# Power.net
KiCad netlist of a schematic drawn in Altium Designer
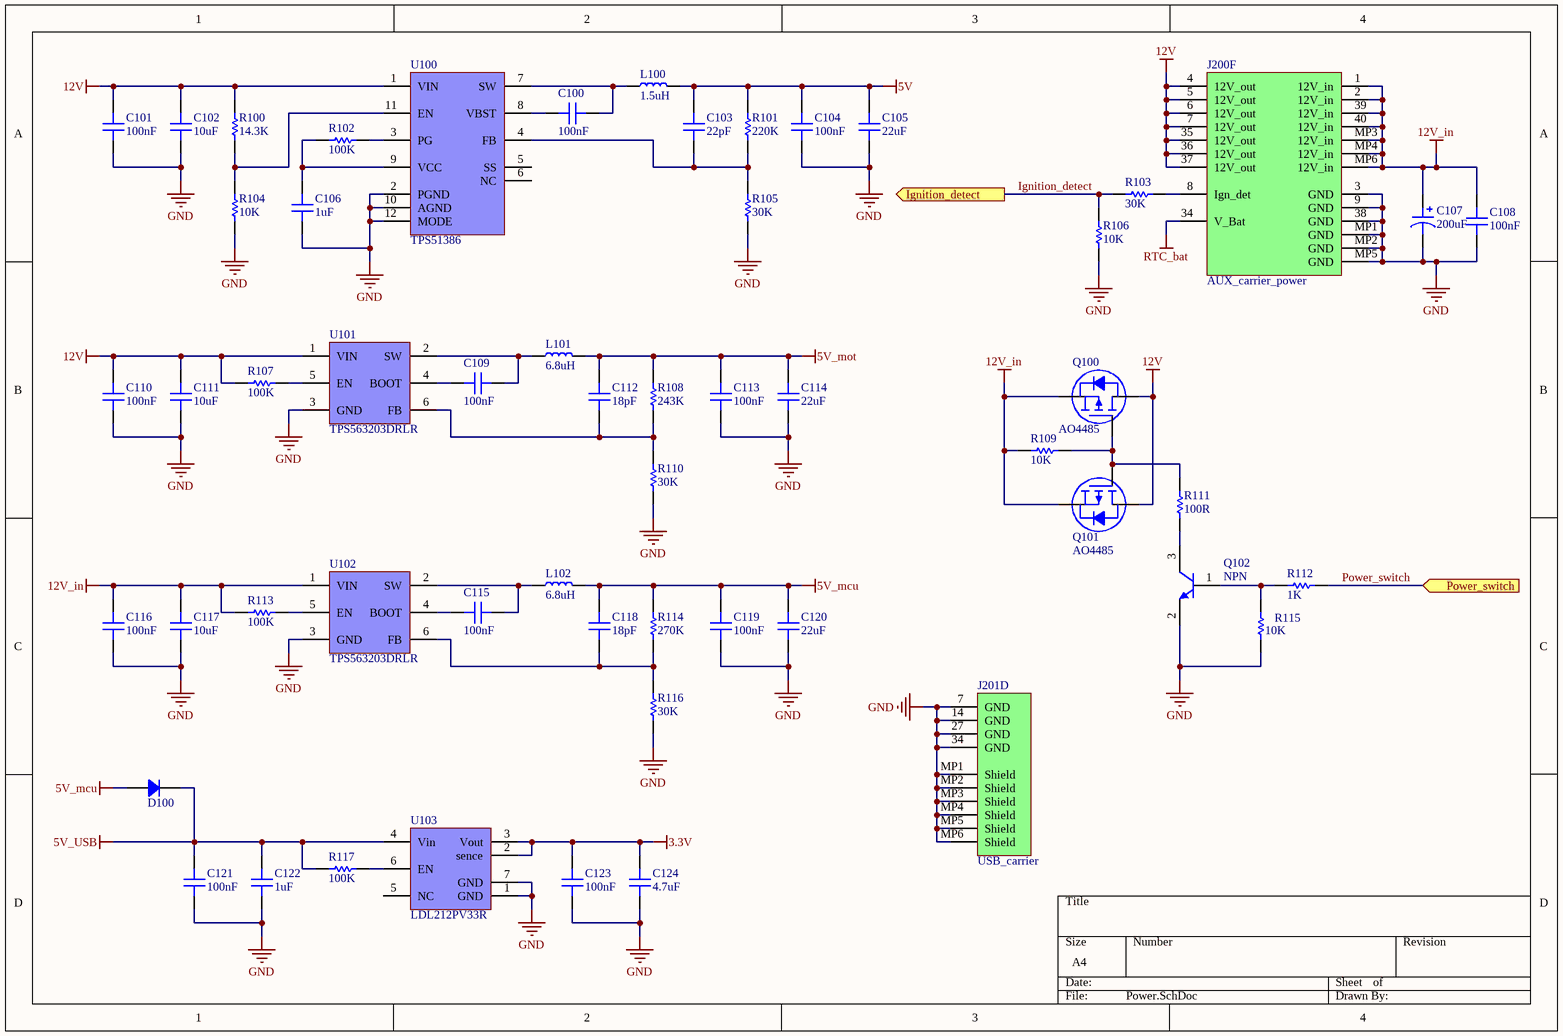
[diagram p0: Power.SchDoc]

(export (version "E")
  (design (tool "Eeschema 10.0.6"))
  (components
    (comp (ref "C100")
      (value "100nF")
      (footprint "CAP 0603")
      (description "SMT Capacitor")
      (libsource (lib "Schlib1") (part "Capacitor"))
    )
    (comp (ref "C101")
      (value "100nF")
      (footprint "CAP 0603")
      (description "SMT Capacitor")
      (libsource (lib "Schlib1") (part "Capacitor"))
    )
    (comp (ref "C102")
      (value "10uF")
      (footprint "CAP 1206")
      (description "SMT Capacitor")
      (libsource (lib "Schlib1") (part "Capacitor"))
    )
    (comp (ref "C103")
      (value "22pF")
      (footprint "CAP 0603")
      (description "SMT Capacitor")
      (libsource (lib "Schlib1") (part "Capacitor"))
    )
    (comp (ref "C104")
      (value "100nF")
      (footprint "CAP 0603")
      (description "SMT Capacitor")
      (libsource (lib "Schlib1") (part "Capacitor"))
    )
    (comp (ref "C105")
      (value "22uF")
      (footprint "CAP 1206")
      (description "SMT Capacitor")
      (libsource (lib "Schlib1") (part "Capacitor"))
    )
    (comp (ref "C106")
      (value "1uF")
      (footprint "CAP 0603")
      (description "SMT Capacitor")
      (libsource (lib "Schlib1") (part "Capacitor"))
    )
    (comp (ref "C107")
      (value "200uF")
      (footprint "CAP ALSMD ELEC 6.6MM H5.7MM")
      (description "SMT Polarised Capacitor")
      (libsource (lib "Schlib1") (part "Capacitor polarized"))
    )
    (comp (ref "C108")
      (value "100nF")
      (footprint "CAP 0603")
      (description "SMT Capacitor")
      (libsource (lib "Schlib1") (part "Capacitor"))
    )
    (comp (ref "C109")
      (value "100nF")
      (footprint "CAP 0603")
      (description "SMT Capacitor")
      (libsource (lib "Schlib1") (part "Capacitor"))
    )
    (comp (ref "C110")
      (value "100nF")
      (footprint "CAP 0603")
      (description "SMT Capacitor")
      (libsource (lib "Schlib1") (part "Capacitor"))
    )
    (comp (ref "C111")
      (value "10uF")
      (footprint "CAP 1206")
      (description "SMT Capacitor")
      (libsource (lib "Schlib1") (part "Capacitor"))
    )
    (comp (ref "C112")
      (value "18pF")
      (footprint "CAP 0603")
      (description "SMT Capacitor")
      (libsource (lib "Schlib1") (part "Capacitor"))
    )
    (comp (ref "C113")
      (value "100nF")
      (footprint "CAP 0603")
      (description "SMT Capacitor")
      (libsource (lib "Schlib1") (part "Capacitor"))
    )
    (comp (ref "C114")
      (value "22uF")
      (footprint "CAP 1206")
      (description "SMT Capacitor")
      (libsource (lib "Schlib1") (part "Capacitor"))
    )
    (comp (ref "C115")
      (value "100nF")
      (footprint "CAP 0603")
      (description "SMT Capacitor")
      (libsource (lib "Schlib1") (part "Capacitor"))
    )
    (comp (ref "C116")
      (value "100nF")
      (footprint "CAP 0603")
      (description "SMT Capacitor")
      (libsource (lib "Schlib1") (part "Capacitor"))
    )
    (comp (ref "C117")
      (value "10uF")
      (footprint "CAP 1206")
      (description "SMT Capacitor")
      (libsource (lib "Schlib1") (part "Capacitor"))
    )
    (comp (ref "C118")
      (value "18pF")
      (footprint "CAP 0603")
      (description "SMT Capacitor")
      (libsource (lib "Schlib1") (part "Capacitor"))
    )
    (comp (ref "C119")
      (value "100nF")
      (footprint "CAP 0603")
      (description "SMT Capacitor")
      (libsource (lib "Schlib1") (part "Capacitor"))
    )
    (comp (ref "C120")
      (value "22uF")
      (footprint "CAP 1206")
      (description "SMT Capacitor")
      (libsource (lib "Schlib1") (part "Capacitor"))
    )
    (comp (ref "C121")
      (value "100nF")
      (footprint "CAP 0603")
      (description "SMT Capacitor")
      (libsource (lib "Schlib1") (part "Capacitor"))
    )
    (comp (ref "C122")
      (value "1uF")
      (footprint "CAP 0603")
      (description "SMT Capacitor")
      (libsource (lib "Schlib1") (part "Capacitor"))
    )
    (comp (ref "C123")
      (value "100nF")
      (footprint "CAP 0603")
      (description "SMT Capacitor")
      (libsource (lib "Schlib1") (part "Capacitor"))
    )
    (comp (ref "C124")
      (value "4.7uF")
      (footprint "CAP 1206")
      (description "SMT Capacitor")
      (libsource (lib "Schlib1") (part "Capacitor"))
    )
    (comp (ref "D100")
      (value "~")
      (footprint "Bourns DO214AC SMA - duplicate")
      (description "Rectifier Diode")
      (libsource (lib "Schlib1") (part "Diode"))
    )
    (comp (ref "J200")
      (value "AUX_carrier_power")
      (footprint "2167010409")
      (libsource (lib "Schlib1") (part "AUX_carrier"))
    )
    (comp (ref "J201")
      (value "USB_carrier")
      (footprint "2167010409")
      (libsource (lib "Schlib1") (part "USB_carrier"))
    )
    (comp (ref "L100")
      (value "1.5uH")
      (footprint "IND 0806_2016")
      (description "SMT Inductor")
      (libsource (lib "Schlib1") (part "Inductor"))
    )
    (comp (ref "L101")
      (value "6.8uH")
      (footprint "IND 0806_2016")
      (description "SMT Inductor")
      (libsource (lib "Schlib1") (part "Inductor"))
    )
    (comp (ref "L102")
      (value "6.8uH")
      (footprint "IND 0806_2016")
      (description "SMT Inductor")
      (libsource (lib "Schlib1") (part "Inductor"))
    )
    (comp (ref "Q100")
      (value "AO4485")
      (footprint "ALPHAOMEGA SO8 SOP-8L AO4485")
      (description "MOSFET P-CH 40V 10A 8SOIC")
      (fields (field (name "MANUFACTURER") "Alpha & Omega Semiconductor Inc."))
      (libsource (lib "") (part "MOSFET P-CH GDS_1"))
    )
    (comp (ref "Q101")
      (value "AO4485")
      (footprint "ALPHAOMEGA SO8 SOP-8L AO4485")
      (description "MOSFET P-CH 40V 10A 8SOIC")
      (fields (field (name "MANUFACTURER") "Alpha & Omega Semiconductor Inc."))
      (libsource (lib "Celestial Altium Library - altium_library") (part "MOSFET P-CH GDS"))
    )
    (comp (ref "Q102") (value "NPN") (footprint "SOT-23") (libsource (lib "Schlib1") (part "NPN")))
    (comp (ref "R100")
      (value "14.3K")
      (footprint "RES 0603")
      (description "Resistor")
      (fields (field (name "PUBLISHER") "Altium Limited"))
      (libsource (lib "Schlib1") (part "Res"))
    )
    (comp (ref "R101")
      (value "220K")
      (footprint "RES 0603")
      (description "Resistor")
      (fields (field (name "PUBLISHER") "Altium Limited"))
      (libsource (lib "Schlib1") (part "Res"))
    )
    (comp (ref "R102")
      (value "100K")
      (footprint "RES 0603")
      (description "Resistor")
      (fields (field (name "PUBLISHER") "Altium Limited"))
      (libsource (lib "Schlib1") (part "Res"))
    )
    (comp (ref "R103")
      (value "30K")
      (footprint "RES 0603")
      (description "Resistor")
      (fields (field (name "PUBLISHER") "Altium Limited"))
      (libsource (lib "Schlib1") (part "Res"))
    )
    (comp (ref "R104")
      (value "10K")
      (footprint "RES 0603")
      (description "Resistor")
      (fields (field (name "PUBLISHER") "Altium Limited"))
      (libsource (lib "Schlib1") (part "Res"))
    )
    (comp (ref "R105")
      (value "30K")
      (footprint "RES 0603")
      (description "Resistor")
      (fields (field (name "PUBLISHER") "Altium Limited"))
      (libsource (lib "Schlib1") (part "Res"))
    )
    (comp (ref "R106")
      (value "10K")
      (footprint "RES 0603")
      (description "Resistor")
      (fields (field (name "PUBLISHER") "Altium Limited"))
      (libsource (lib "Schlib1") (part "Res"))
    )
    (comp (ref "R107")
      (value "100K")
      (footprint "RES 0603")
      (description "Resistor")
      (fields (field (name "PUBLISHER") "Altium Limited"))
      (libsource (lib "Schlib1") (part "Res"))
    )
    (comp (ref "R108")
      (value "243K")
      (footprint "RES 0603")
      (description "Resistor")
      (fields (field (name "PUBLISHER") "Altium Limited"))
      (libsource (lib "Schlib1") (part "Res"))
    )
    (comp (ref "R109")
      (value "10K")
      (footprint "RES 0603")
      (description "Resistor")
      (fields (field (name "PUBLISHER") "Altium Limited"))
      (libsource (lib "Schlib1") (part "Res"))
    )
    (comp (ref "R110")
      (value "30K")
      (footprint "RES 0603")
      (description "Resistor")
      (fields (field (name "PUBLISHER") "Altium Limited"))
      (libsource (lib "Schlib1") (part "Res"))
    )
    (comp (ref "R111")
      (value "100R")
      (footprint "RES 0603")
      (description "Resistor")
      (fields (field (name "PUBLISHER") "Altium Limited"))
      (libsource (lib "Schlib1") (part "Res"))
    )
    (comp (ref "R112")
      (value "1K")
      (footprint "RES 0603")
      (description "Resistor")
      (fields (field (name "PUBLISHER") "Altium Limited"))
      (libsource (lib "Schlib1") (part "Res"))
    )
    (comp (ref "R113")
      (value "100K")
      (footprint "RES 0603")
      (description "Resistor")
      (fields (field (name "PUBLISHER") "Altium Limited"))
      (libsource (lib "Schlib1") (part "Res"))
    )
    (comp (ref "R114")
      (value "270K")
      (footprint "RES 0603")
      (description "Resistor")
      (fields (field (name "PUBLISHER") "Altium Limited"))
      (libsource (lib "Schlib1") (part "Res"))
    )
    (comp (ref "R115")
      (value "10K")
      (footprint "RES 0603")
      (description "Resistor")
      (fields (field (name "PUBLISHER") "Altium Limited"))
      (libsource (lib "Schlib1") (part "Res"))
    )
    (comp (ref "R116")
      (value "30K")
      (footprint "RES 0603")
      (description "Resistor")
      (fields (field (name "PUBLISHER") "Altium Limited"))
      (libsource (lib "Schlib1") (part "Res"))
    )
    (comp (ref "R117")
      (value "100K")
      (footprint "RES 0603")
      (description "Resistor")
      (fields (field (name "PUBLISHER") "Altium Limited"))
      (libsource (lib "Schlib1") (part "Res"))
    )
    (comp (ref "U100")
      (value "TPS51386")
      (footprint "VREG_TPS51386RJNR")
      (libsource (lib "Schlib1") (part "TPS51386"))
    )
    (comp (ref "U101")
      (value "TPS563203DRLR")
      (footprint "TI SOT-563 DRL")
      (libsource (lib "Schlib1") (part "TPS563203DRLR"))
    )
    (comp (ref "U102")
      (value "TPS563203DRLR")
      (footprint "TI SOT-563 DRL")
      (libsource (lib "Schlib1") (part "TPS563203DRLR"))
    )
    (comp (ref "U103")
      (value "LDL212PV33R")
      (footprint "SON50P200X200X80-7N-D")
      (libsource (lib "Schlib1") (part "LDL212PV33R"))
    )
  )
  (nets
    (net (code "1") (name "/Ignition_detect") (class "Default")
      (node (ref "R103") (pin "2") (pinfunction "2_2") (pintype "passive"))
      (node (ref "R106") (pin "1") (pinfunction "1_1") (pintype "passive"))
    )
    (net (code "2") (name "/Power_switch") (class "Default")
      (node (ref "R112") (pin "1") (pinfunction "1_1") (pintype "passive"))
    )
    (net (code "3") (name "3.3V") (class "Default")
      (node (ref "C123") (pin "2") (pinfunction "2_2") (pintype "passive"))
      (node (ref "C124") (pin "2") (pinfunction "2_2") (pintype "passive"))
      (node (ref "U103") (pin "2") (pinfunction "sence_2") (pintype "passive"))
      (node (ref "U103") (pin "3") (pinfunction "Vout_3") (pintype "passive"))
    )
    (net (code "4") (name "5V") (class "Default")
      (node (ref "C103") (pin "2") (pinfunction "2_2") (pintype "passive"))
      (node (ref "C104") (pin "2") (pinfunction "2_2") (pintype "passive"))
      (node (ref "C105") (pin "2") (pinfunction "2_2") (pintype "passive"))
      (node (ref "L100") (pin "2") (pinfunction "2_2") (pintype "passive"))
      (node (ref "R101") (pin "2") (pinfunction "2_2") (pintype "passive"))
    )
    (net (code "5") (name "5V_USB") (class "Default")
      (node (ref "C121") (pin "2") (pinfunction "2_2") (pintype "passive"))
      (node (ref "C122") (pin "2") (pinfunction "2_2") (pintype "passive"))
      (node (ref "D100") (pin "2") (pinfunction "2_2") (pintype "passive"))
      (node (ref "R117") (pin "1") (pinfunction "1_1") (pintype "passive"))
      (node (ref "U103") (pin "4") (pinfunction "Vin_4") (pintype "passive"))
    )
    (net (code "6") (name "5V_mcu") (class "Default")
      (node (ref "C118") (pin "2") (pinfunction "2_2") (pintype "passive"))
      (node (ref "C119") (pin "2") (pinfunction "2_2") (pintype "passive"))
      (node (ref "C120") (pin "2") (pinfunction "2_2") (pintype "passive"))
      (node (ref "D100") (pin "1") (pinfunction "1_1") (pintype "passive"))
      (node (ref "L102") (pin "2") (pinfunction "2_2") (pintype "passive"))
      (node (ref "R114") (pin "2") (pinfunction "2_2") (pintype "passive"))
    )
    (net (code "7") (name "5V_mot") (class "Default")
      (node (ref "C112") (pin "2") (pinfunction "2_2") (pintype "passive"))
      (node (ref "C113") (pin "2") (pinfunction "2_2") (pintype "passive"))
      (node (ref "C114") (pin "2") (pinfunction "2_2") (pintype "passive"))
      (node (ref "L101") (pin "2") (pinfunction "2_2") (pintype "passive"))
      (node (ref "R108") (pin "2") (pinfunction "2_2") (pintype "passive"))
    )
    (net (code "8") (name "12V") (class "Default")
      (node (ref "C101") (pin "2") (pinfunction "2_2") (pintype "passive"))
      (node (ref "C102") (pin "2") (pinfunction "2_2") (pintype "passive"))
      (node (ref "C110") (pin "2") (pinfunction "2_2") (pintype "passive"))
      (node (ref "C111") (pin "2") (pinfunction "2_2") (pintype "passive"))
      (node (ref "J200") (pin "35") (pinfunction "12V_out_35") (pintype "passive"))
      (node (ref "J200") (pin "36") (pinfunction "12V_out_36") (pintype "passive"))
      (node (ref "J200") (pin "37") (pinfunction "12V_out_37") (pintype "passive"))
      (node (ref "J200") (pin "4") (pinfunction "12V_out_4") (pintype "passive"))
      (node (ref "J200") (pin "5") (pinfunction "12V_out_5") (pintype "passive"))
      (node (ref "J200") (pin "6") (pinfunction "12V_out_6") (pintype "passive"))
      (node (ref "J200") (pin "7") (pinfunction "12V_out_7") (pintype "passive"))
      (node (ref "Q100") (pin "D") (pinfunction "D_D") (pintype "passive"))
      (node (ref "Q101") (pin "D") (pinfunction "D_D") (pintype "passive"))
      (node (ref "R100") (pin "1") (pinfunction "1_1") (pintype "passive"))
      (node (ref "R107") (pin "1") (pinfunction "1_1") (pintype "passive"))
      (node (ref "U100") (pin "1") (pinfunction "VIN_1") (pintype "passive"))
      (node (ref "U101") (pin "1") (pinfunction "VIN_1") (pintype "passive"))
    )
    (net (code "9") (name "12V_in") (class "Default")
      (node (ref "C107") (pin "2") (pinfunction "2_2") (pintype "passive"))
      (node (ref "C108") (pin "2") (pinfunction "2_2") (pintype "passive"))
      (node (ref "C116") (pin "2") (pinfunction "2_2") (pintype "passive"))
      (node (ref "C117") (pin "2") (pinfunction "2_2") (pintype "passive"))
      (node (ref "J200") (pin "1") (pinfunction "12V_in_1") (pintype "passive"))
      (node (ref "J200") (pin "2") (pinfunction "12V_in_2") (pintype "passive"))
      (node (ref "J200") (pin "39") (pinfunction "12V_in_39") (pintype "passive"))
      (node (ref "J200") (pin "40") (pinfunction "12V_in_40") (pintype "passive"))
      (node (ref "J200") (pin "MP3") (pinfunction "12V_in_MP3") (pintype "passive"))
      (node (ref "J200") (pin "MP4") (pinfunction "12V_in_MP4") (pintype "passive"))
      (node (ref "J200") (pin "MP6") (pinfunction "12V_in_MP6") (pintype "passive"))
      (node (ref "Q100") (pin "S") (pinfunction "S_S") (pintype "passive"))
      (node (ref "Q101") (pin "S") (pinfunction "S_S") (pintype "passive"))
      (node (ref "R109") (pin "2") (pinfunction "2_2") (pintype "passive"))
      (node (ref "R113") (pin "1") (pinfunction "1_1") (pintype "passive"))
      (node (ref "U102") (pin "1") (pinfunction "VIN_1") (pintype "passive"))
    )
    (net (code "10") (name "GND") (class "Default")
      (node (ref "C101") (pin "1") (pinfunction "1_1") (pintype "passive"))
      (node (ref "C102") (pin "1") (pinfunction "1_1") (pintype "passive"))
      (node (ref "C104") (pin "1") (pinfunction "1_1") (pintype "passive"))
      (node (ref "C105") (pin "1") (pinfunction "1_1") (pintype "passive"))
      (node (ref "C106") (pin "1") (pinfunction "1_1") (pintype "passive"))
      (node (ref "C107") (pin "1") (pinfunction "1_1") (pintype "passive"))
      (node (ref "C108") (pin "1") (pinfunction "1_1") (pintype "passive"))
      (node (ref "C110") (pin "1") (pinfunction "1_1") (pintype "passive"))
      (node (ref "C111") (pin "1") (pinfunction "1_1") (pintype "passive"))
      (node (ref "C113") (pin "1") (pinfunction "1_1") (pintype "passive"))
      (node (ref "C114") (pin "1") (pinfunction "1_1") (pintype "passive"))
      (node (ref "C116") (pin "1") (pinfunction "1_1") (pintype "passive"))
      (node (ref "C117") (pin "1") (pinfunction "1_1") (pintype "passive"))
      (node (ref "C119") (pin "1") (pinfunction "1_1") (pintype "passive"))
      (node (ref "C120") (pin "1") (pinfunction "1_1") (pintype "passive"))
      (node (ref "C121") (pin "1") (pinfunction "1_1") (pintype "passive"))
      (node (ref "C122") (pin "1") (pinfunction "1_1") (pintype "passive"))
      (node (ref "C123") (pin "1") (pinfunction "1_1") (pintype "passive"))
      (node (ref "C124") (pin "1") (pinfunction "1_1") (pintype "passive"))
      (node (ref "J200") (pin "3") (pinfunction "GND_3") (pintype "passive"))
      (node (ref "J200") (pin "38") (pinfunction "GND_38") (pintype "passive"))
      (node (ref "J200") (pin "9") (pinfunction "GND_9") (pintype "passive"))
      (node (ref "J200") (pin "MP1") (pinfunction "GND_MP1") (pintype "passive"))
      (node (ref "J200") (pin "MP2") (pinfunction "GND_MP2") (pintype "passive"))
      (node (ref "J200") (pin "MP5") (pinfunction "GND_MP5") (pintype "passive"))
      (node (ref "J201") (pin "14") (pinfunction "GND_14") (pintype "passive"))
      (node (ref "J201") (pin "27") (pinfunction "GND_27") (pintype "passive"))
      (node (ref "J201") (pin "34") (pinfunction "GND_34") (pintype "passive"))
      (node (ref "J201") (pin "7") (pinfunction "GND_7") (pintype "passive"))
      (node (ref "J201") (pin "MP1") (pinfunction "Shield_MP1") (pintype "passive"))
      (node (ref "J201") (pin "MP2") (pinfunction "Shield_MP2") (pintype "passive"))
      (node (ref "J201") (pin "MP3") (pinfunction "Shield_MP3") (pintype "passive"))
      (node (ref "J201") (pin "MP4") (pinfunction "Shield_MP4") (pintype "passive"))
      (node (ref "J201") (pin "MP5") (pinfunction "Shield_MP5") (pintype "passive"))
      (node (ref "J201") (pin "MP6") (pinfunction "Shield_MP6") (pintype "passive"))
      (node (ref "Q102") (pin "2") (pinfunction "E_2") (pintype "passive"))
      (node (ref "R104") (pin "1") (pinfunction "1_1") (pintype "passive"))
      (node (ref "R105") (pin "1") (pinfunction "1_1") (pintype "passive"))
      (node (ref "R106") (pin "2") (pinfunction "2_2") (pintype "passive"))
      (node (ref "R110") (pin "1") (pinfunction "1_1") (pintype "passive"))
      (node (ref "R115") (pin "2") (pinfunction "2_2") (pintype "passive"))
      (node (ref "R116") (pin "1") (pinfunction "1_1") (pintype "passive"))
      (node (ref "U100") (pin "10") (pinfunction "AGND_10") (pintype "passive"))
      (node (ref "U100") (pin "12") (pinfunction "MODE_12") (pintype "passive"))
      (node (ref "U100") (pin "2") (pinfunction "PGND_2") (pintype "passive"))
      (node (ref "U101") (pin "3") (pinfunction "GND_3") (pintype "passive"))
      (node (ref "U102") (pin "3") (pinfunction "GND_3") (pintype "passive"))
      (node (ref "U103") (pin "1") (pinfunction "GND_1") (pintype "passive"))
      (node (ref "U103") (pin "7") (pinfunction "GND_7") (pintype "passive"))
    )
    (net (code "11") (name "Net-(J200F-Ign_det)") (class "Default")
      (node (ref "J200") (pin "8") (pinfunction "Ign_det_8") (pintype "passive"))
      (node (ref "R103") (pin "1") (pinfunction "1_1") (pintype "passive"))
    )
    (net (code "12") (name "Net-(Q100-PadG)") (class "Default")
      (node (ref "Q100") (pin "G") (pinfunction "G_G") (pintype "passive"))
      (node (ref "Q101") (pin "G") (pinfunction "G_G") (pintype "passive"))
      (node (ref "R109") (pin "1") (pinfunction "1_1") (pintype "passive"))
      (node (ref "R111") (pin "1") (pinfunction "1_1") (pintype "passive"))
    )
    (net (code "13") (name "Net-(Q102-B)") (class "Default")
      (node (ref "Q102") (pin "1") (pinfunction "B_1") (pintype "passive"))
      (node (ref "R112") (pin "2") (pinfunction "2_2") (pintype "passive"))
      (node (ref "R115") (pin "1") (pinfunction "1_1") (pintype "passive"))
    )
    (net (code "14") (name "Net-(Q102-C)") (class "Default")
      (node (ref "Q102") (pin "3") (pinfunction "C_3") (pintype "passive"))
      (node (ref "R111") (pin "2") (pinfunction "2_2") (pintype "passive"))
    )
    (net (code "15") (name "Net-(U100-EN)") (class "Default")
      (node (ref "R100") (pin "2") (pinfunction "2_2") (pintype "passive"))
      (node (ref "R104") (pin "2") (pinfunction "2_2") (pintype "passive"))
      (node (ref "U100") (pin "11") (pinfunction "EN_11") (pintype "passive"))
    )
    (net (code "16") (name "Net-(U100-FB)") (class "Default")
      (node (ref "C103") (pin "1") (pinfunction "1_1") (pintype "passive"))
      (node (ref "R101") (pin "1") (pinfunction "1_1") (pintype "passive"))
      (node (ref "R105") (pin "2") (pinfunction "2_2") (pintype "passive"))
      (node (ref "U100") (pin "4") (pinfunction "FB_4") (pintype "passive"))
    )
    (net (code "17") (name "Net-(U100-PG)") (class "Default")
      (node (ref "R102") (pin "2") (pinfunction "2_2") (pintype "passive"))
      (node (ref "U100") (pin "3") (pinfunction "PG_3") (pintype "passive"))
    )
    (net (code "18") (name "Net-(U100-SW)") (class "Default")
      (node (ref "C100") (pin "1") (pinfunction "1_1") (pintype "passive"))
      (node (ref "L100") (pin "1") (pinfunction "1_1") (pintype "passive"))
      (node (ref "U100") (pin "7") (pinfunction "SW_7") (pintype "passive"))
    )
    (net (code "19") (name "Net-(U100-VBST)") (class "Default")
      (node (ref "C100") (pin "2") (pinfunction "2_2") (pintype "passive"))
      (node (ref "U100") (pin "8") (pinfunction "VBST_8") (pintype "passive"))
    )
    (net (code "20") (name "Net-(U100-VCC)") (class "Default")
      (node (ref "C106") (pin "2") (pinfunction "2_2") (pintype "passive"))
      (node (ref "R102") (pin "1") (pinfunction "1_1") (pintype "passive"))
      (node (ref "U100") (pin "9") (pinfunction "VCC_9") (pintype "passive"))
    )
    (net (code "21") (name "Net-(U101-BOOT)") (class "Default")
      (node (ref "C109") (pin "2") (pinfunction "2_2") (pintype "passive"))
      (node (ref "U101") (pin "4") (pinfunction "BOOT_4") (pintype "passive"))
    )
    (net (code "22") (name "Net-(U101-EN)") (class "Default")
      (node (ref "R107") (pin "2") (pinfunction "2_2") (pintype "passive"))
      (node (ref "U101") (pin "5") (pinfunction "EN_5") (pintype "passive"))
    )
    (net (code "23") (name "Net-(U101-FB)") (class "Default")
      (node (ref "C112") (pin "1") (pinfunction "1_1") (pintype "passive"))
      (node (ref "R108") (pin "1") (pinfunction "1_1") (pintype "passive"))
      (node (ref "R110") (pin "2") (pinfunction "2_2") (pintype "passive"))
      (node (ref "U101") (pin "6") (pinfunction "FB_6") (pintype "passive"))
    )
    (net (code "24") (name "Net-(U101-SW)") (class "Default")
      (node (ref "C109") (pin "1") (pinfunction "1_1") (pintype "passive"))
      (node (ref "L101") (pin "1") (pinfunction "1_1") (pintype "passive"))
      (node (ref "U101") (pin "2") (pinfunction "SW_2") (pintype "passive"))
    )
    (net (code "25") (name "Net-(U102-BOOT)") (class "Default")
      (node (ref "C115") (pin "2") (pinfunction "2_2") (pintype "passive"))
      (node (ref "U102") (pin "4") (pinfunction "BOOT_4") (pintype "passive"))
    )
    (net (code "26") (name "Net-(U102-EN)") (class "Default")
      (node (ref "R113") (pin "2") (pinfunction "2_2") (pintype "passive"))
      (node (ref "U102") (pin "5") (pinfunction "EN_5") (pintype "passive"))
    )
    (net (code "27") (name "Net-(U102-FB)") (class "Default")
      (node (ref "C118") (pin "1") (pinfunction "1_1") (pintype "passive"))
      (node (ref "R114") (pin "1") (pinfunction "1_1") (pintype "passive"))
      (node (ref "R116") (pin "2") (pinfunction "2_2") (pintype "passive"))
      (node (ref "U102") (pin "6") (pinfunction "FB_6") (pintype "passive"))
    )
    (net (code "28") (name "Net-(U102-SW)") (class "Default")
      (node (ref "C115") (pin "1") (pinfunction "1_1") (pintype "passive"))
      (node (ref "L102") (pin "1") (pinfunction "1_1") (pintype "passive"))
      (node (ref "U102") (pin "2") (pinfunction "SW_2") (pintype "passive"))
    )
    (net (code "29") (name "Net-(U103-EN)") (class "Default")
      (node (ref "R117") (pin "2") (pinfunction "2_2") (pintype "passive"))
      (node (ref "U103") (pin "6") (pinfunction "EN_6") (pintype "passive"))
    )
    (net (code "30") (name "RTC_bat") (class "Default")
      (node (ref "J200") (pin "34") (pinfunction "V_Bat_34") (pintype "passive"))
    )
    (net (code "31") (name "unconnected-(U100-NC-Pad6)") (class "Default")
      (node (ref "U100") (pin "6") (pinfunction "NC_6") (pintype "passive"))
    )
    (net (code "32") (name "unconnected-(U100-SS-Pad5)") (class "Default")
      (node (ref "U100") (pin "5") (pinfunction "SS_5") (pintype "passive"))
    )
    (net (code "33") (name "unconnected-(U103-NC-Pad5)") (class "Default")
      (node (ref "U103") (pin "5") (pinfunction "NC_5") (pintype "passive"))
    )
  )
)
